# shield.net
KiCad netlist of a schematic drawn in EAGLE
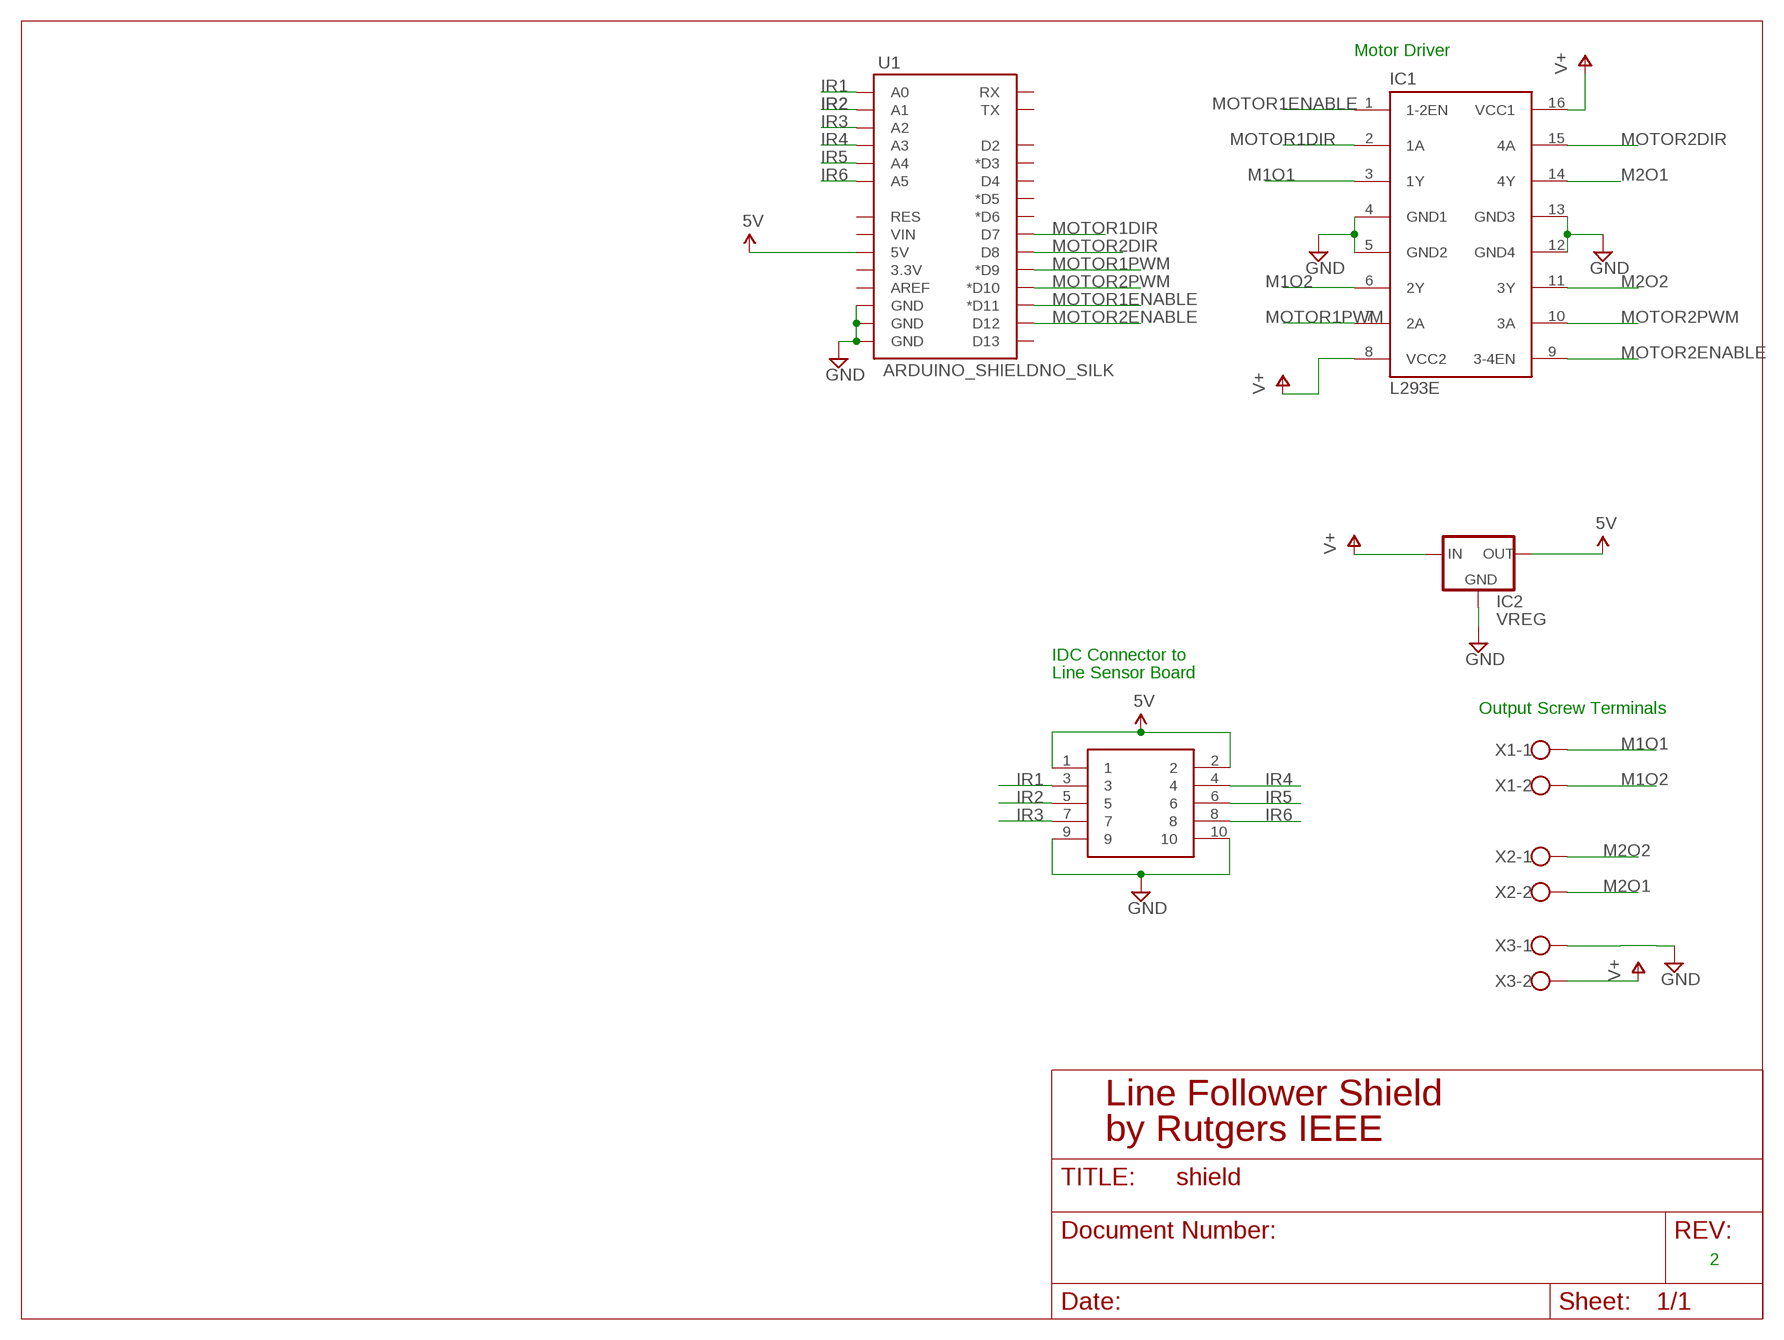
[diagram p0: schematic, sheet 1]

(export (version "E")
  (design (tool "Eeschema 10.0.6"))
  (components
    (comp (ref "IC1")
      (value "L293E")
      (footprint "eagle-import:DIL16")
      (libsource (lib "eagle-import") (part "L293E"))
    )
    (comp (ref "IC2")
      (value "VREG")
      (footprint "eagle-import:TO-220-ALT")
      (libsource (lib "eagle-import") (part "V_REG_78XX-TO-220"))
    )
    (comp (ref "U$3")
      (value "2X5-PHEADER")
      (footprint "eagle-import:2X5-SHROUDED-HEADER")
      (libsource (lib "eagle-import") (part "2X5-PHEADER"))
    )
    (comp (ref "U1")
      (value "ARDUINO_SHIELDNO_SILK")
      (footprint "eagle-import:DUEMILANOVE_VIAS")
      (libsource (lib "eagle-import") (part "ARDUINO_SHIELDNO_SILK"))
    )
    (comp (ref "X1")
      (value "W237-102")
      (footprint "eagle-import:W237-102")
      (libsource (lib "eagle-import") (part "W237-102"))
    )
    (comp (ref "X2")
      (value "W237-102")
      (footprint "eagle-import:W237-102")
      (libsource (lib "eagle-import") (part "W237-102"))
    )
    (comp (ref "X3")
      (value "W237-102")
      (footprint "eagle-import:W237-102")
      (libsource (lib "eagle-import") (part "W237-102"))
    )
  )
  (nets
    (net (code "1") (name "/IR1") (class "Default")
      (node (ref "U$3") (pin "3") (pinfunction "3_3") (pintype "bidirectional"))
      (node (ref "U1") (pin "A0") (pinfunction "A0_A0") (pintype "bidirectional"))
    )
    (net (code "2") (name "/IR2") (class "Default")
      (node (ref "U$3") (pin "5") (pinfunction "5_5") (pintype "bidirectional"))
      (node (ref "U1") (pin "A1") (pinfunction "A1_A1") (pintype "bidirectional"))
    )
    (net (code "3") (name "/IR3") (class "Default")
      (node (ref "U$3") (pin "7") (pinfunction "7_7") (pintype "bidirectional"))
      (node (ref "U1") (pin "A2") (pinfunction "A2_A2") (pintype "bidirectional"))
    )
    (net (code "4") (name "/IR4") (class "Default")
      (node (ref "U$3") (pin "4") (pinfunction "4_4") (pintype "bidirectional"))
      (node (ref "U1") (pin "A3") (pinfunction "A3_A3") (pintype "bidirectional"))
    )
    (net (code "5") (name "/IR5") (class "Default")
      (node (ref "U$3") (pin "6") (pinfunction "6_6") (pintype "bidirectional"))
      (node (ref "U1") (pin "A4") (pinfunction "A4_A4") (pintype "bidirectional"))
    )
    (net (code "6") (name "/IR6") (class "Default")
      (node (ref "U$3") (pin "8") (pinfunction "8_8") (pintype "bidirectional"))
      (node (ref "U1") (pin "A5") (pinfunction "A5_A5") (pintype "bidirectional"))
    )
    (net (code "7") (name "/M1O1") (class "Default")
      (node (ref "IC1") (pin "3") (pinfunction "1Y_3") (pintype "output"))
      (node (ref "X1") (pin "1") (pinfunction "KL_1") (pintype "passive"))
    )
    (net (code "8") (name "/M1O2") (class "Default")
      (node (ref "IC1") (pin "6") (pinfunction "2Y_6") (pintype "output"))
      (node (ref "X1") (pin "2") (pinfunction "KL_2") (pintype "passive"))
    )
    (net (code "9") (name "/M2O1") (class "Default")
      (node (ref "IC1") (pin "14") (pinfunction "4Y_14") (pintype "output"))
      (node (ref "X2") (pin "2") (pinfunction "KL_2") (pintype "passive"))
    )
    (net (code "10") (name "/M2O2") (class "Default")
      (node (ref "IC1") (pin "11") (pinfunction "3Y_11") (pintype "output"))
      (node (ref "X2") (pin "1") (pinfunction "KL_1") (pintype "passive"))
    )
    (net (code "11") (name "/MOTOR1DIR") (class "Default")
      (node (ref "IC1") (pin "2") (pinfunction "1A_2") (pintype "input"))
      (node (ref "U1") (pin "D7") (pinfunction "D7_D7") (pintype "bidirectional"))
    )
    (net (code "12") (name "/MOTOR1ENABLE") (class "Default")
      (node (ref "IC1") (pin "1") (pinfunction "1-2EN_1") (pintype "input"))
      (node (ref "U1") (pin "D11") (pinfunction "*D11_D11") (pintype "bidirectional"))
    )
    (net (code "13") (name "/MOTOR1PWM") (class "Default")
      (node (ref "IC1") (pin "7") (pinfunction "2A_7") (pintype "input"))
      (node (ref "U1") (pin "D9") (pinfunction "*D9_D9") (pintype "bidirectional"))
    )
    (net (code "14") (name "/MOTOR2DIR") (class "Default")
      (node (ref "IC1") (pin "15") (pinfunction "4A_15") (pintype "input"))
      (node (ref "U1") (pin "D8") (pinfunction "D8_D8") (pintype "bidirectional"))
    )
    (net (code "15") (name "/MOTOR2ENABLE") (class "Default")
      (node (ref "IC1") (pin "9") (pinfunction "3-4EN_9") (pintype "input"))
      (node (ref "U1") (pin "D12") (pinfunction "D12_D12") (pintype "bidirectional"))
    )
    (net (code "16") (name "/MOTOR2PWM") (class "Default")
      (node (ref "IC1") (pin "10") (pinfunction "3A_10") (pintype "input"))
      (node (ref "U1") (pin "D10") (pinfunction "*D10_D10") (pintype "bidirectional"))
    )
    (net (code "17") (name "5V") (class "Default")
      (node (ref "IC2") (pin "OUT") (pinfunction "OUT_OUT") (pintype "output"))
      (node (ref "U$3") (pin "1") (pinfunction "1_1") (pintype "bidirectional"))
      (node (ref "U$3") (pin "2") (pinfunction "2_2") (pintype "bidirectional"))
      (node (ref "U1") (pin "5V") (pinfunction "5V_5V") (pintype "bidirectional"))
    )
    (net (code "18") (name "GND") (class "Default")
      (node (ref "IC1") (pin "12") (pinfunction "GND4_12") (pintype "power_in"))
      (node (ref "IC1") (pin "13") (pinfunction "GND3_13") (pintype "power_in"))
      (node (ref "IC1") (pin "4") (pinfunction "GND1_4") (pintype "power_in"))
      (node (ref "IC1") (pin "5") (pinfunction "GND2_5") (pintype "power_in"))
      (node (ref "IC2") (pin "GND") (pinfunction "GND_GND") (pintype "input"))
      (node (ref "U$3") (pin "10") (pinfunction "10_10") (pintype "bidirectional"))
      (node (ref "U$3") (pin "9") (pinfunction "9_9") (pintype "bidirectional"))
      (node (ref "U1") (pin "GND@0") (pinfunction "GND_GND@0") (pintype "bidirectional"))
      (node (ref "U1") (pin "GND@1") (pinfunction "GND_GND@1") (pintype "bidirectional"))
      (node (ref "U1") (pin "GND@2") (pinfunction "GND_GND@2") (pintype "bidirectional"))
      (node (ref "X3") (pin "1") (pinfunction "KL_1") (pintype "passive"))
    )
    (net (code "19") (name "V+") (class "Default")
      (node (ref "IC1") (pin "16") (pinfunction "VCC1_16") (pintype "power_in"))
      (node (ref "IC1") (pin "8") (pinfunction "VCC2_8") (pintype "power_in"))
      (node (ref "IC2") (pin "IN") (pinfunction "IN_IN") (pintype "input"))
      (node (ref "X3") (pin "2") (pinfunction "KL_2") (pintype "passive"))
    )
    (net (code "20") (name "unconnected-(U1-*D3-PadD3)") (class "Default")
      (node (ref "U1") (pin "D3") (pinfunction "*D3_D3") (pintype "bidirectional"))
    )
    (net (code "21") (name "unconnected-(U1-*D5-PadD5)") (class "Default")
      (node (ref "U1") (pin "D5") (pinfunction "*D5_D5") (pintype "bidirectional"))
    )
    (net (code "22") (name "unconnected-(U1-*D6-PadD6)") (class "Default")
      (node (ref "U1") (pin "D6") (pinfunction "*D6_D6") (pintype "bidirectional"))
    )
    (net (code "23") (name "unconnected-(U1-Pad3.3V)") (class "Default")
      (node (ref "U1") (pin "3.3V") (pinfunction "3.3V_3.3V") (pintype "bidirectional"))
    )
    (net (code "24") (name "unconnected-(U1-PadAREF)") (class "Default")
      (node (ref "U1") (pin "AREF") (pinfunction "AREF_AREF") (pintype "bidirectional"))
    )
    (net (code "25") (name "unconnected-(U1-PadD2)") (class "Default")
      (node (ref "U1") (pin "D2") (pinfunction "D2_D2") (pintype "bidirectional"))
    )
    (net (code "26") (name "unconnected-(U1-PadD4)") (class "Default")
      (node (ref "U1") (pin "D4") (pinfunction "D4_D4") (pintype "bidirectional"))
    )
    (net (code "27") (name "unconnected-(U1-PadD13)") (class "Default")
      (node (ref "U1") (pin "D13") (pinfunction "D13_D13") (pintype "bidirectional"))
    )
    (net (code "28") (name "unconnected-(U1-PadRES)") (class "Default")
      (node (ref "U1") (pin "RES") (pinfunction "RES_RES") (pintype "bidirectional"))
    )
    (net (code "29") (name "unconnected-(U1-PadRX)") (class "Default")
      (node (ref "U1") (pin "RX") (pinfunction "RX_RX") (pintype "bidirectional"))
    )
    (net (code "30") (name "unconnected-(U1-PadTX)") (class "Default")
      (node (ref "U1") (pin "TX") (pinfunction "TX_TX") (pintype "bidirectional"))
    )
    (net (code "31") (name "unconnected-(U1-PadVIN)") (class "Default")
      (node (ref "U1") (pin "VIN") (pinfunction "VIN_VIN") (pintype "bidirectional"))
    )
  )
)
